# 2AFADC.net
KiCad netlist of a schematic drawn in EAGLE
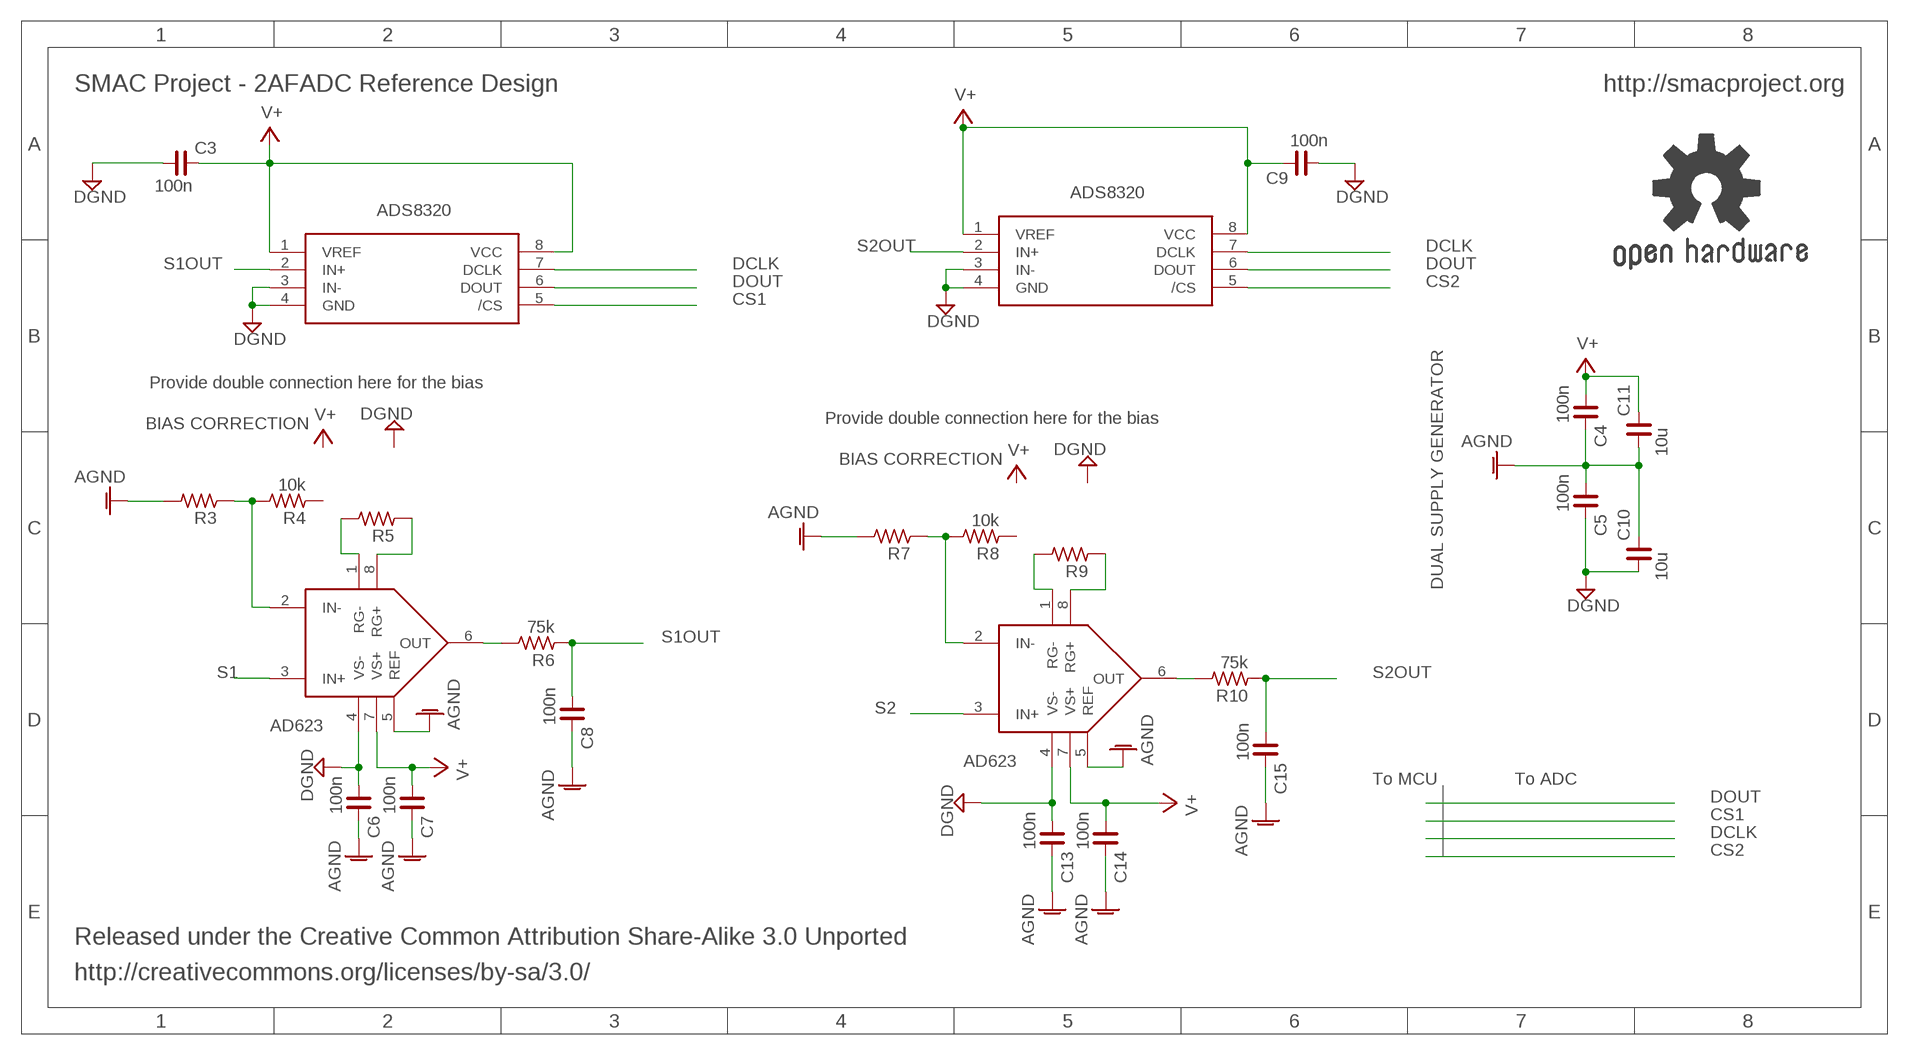
[diagram p0: schematic, sheet 1]

(export (version "E")
  (design (tool "Eeschema 10.0.6"))
  (components
    (comp (ref "C3")
      (value "100n")
      (footprint "eagle-import:C0402")
      (libsource (lib "eagle-import") (part "C_0402"))
    )
    (comp (ref "C4")
      (value "100n")
      (footprint "eagle-import:C0402")
      (libsource (lib "eagle-import") (part "C_0402"))
    )
    (comp (ref "C5")
      (value "100n")
      (footprint "eagle-import:C0402")
      (libsource (lib "eagle-import") (part "C_0402"))
    )
    (comp (ref "C6")
      (value "100n")
      (footprint "eagle-import:C0402")
      (libsource (lib "eagle-import") (part "C_0402"))
    )
    (comp (ref "C7")
      (value "100n")
      (footprint "eagle-import:C0402")
      (libsource (lib "eagle-import") (part "C_0402"))
    )
    (comp (ref "C8")
      (value "100n")
      (footprint "eagle-import:C0402")
      (libsource (lib "eagle-import") (part "C_0402"))
    )
    (comp (ref "C9")
      (value "100n")
      (footprint "eagle-import:C0402")
      (libsource (lib "eagle-import") (part "C_0402"))
    )
    (comp (ref "C10")
      (value "10u")
      (footprint "eagle-import:C0402")
      (libsource (lib "eagle-import") (part "C_0402"))
    )
    (comp (ref "C11")
      (value "10u")
      (footprint "eagle-import:C0402")
      (libsource (lib "eagle-import") (part "C_0402"))
    )
    (comp (ref "C13")
      (value "100n")
      (footprint "eagle-import:C0402")
      (libsource (lib "eagle-import") (part "C_0402"))
    )
    (comp (ref "C14")
      (value "100n")
      (footprint "eagle-import:C0402")
      (libsource (lib "eagle-import") (part "C_0402"))
    )
    (comp (ref "C15")
      (value "100n")
      (footprint "eagle-import:C0402")
      (libsource (lib "eagle-import") (part "C_0402"))
    )
    (comp (ref "GOLD_ORB_SM1")
      (value "OSHWLOGO_REF_SM")
      (footprint "eagle-import:OSHW2REF")
      (libsource (lib "eagle-import") (part "OSHWLOGO_REF_SM"))
    )
    (comp (ref "R3")
      (value "R_0402")
      (footprint "eagle-import:R0402")
      (libsource (lib "eagle-import") (part "R_0402"))
    )
    (comp (ref "R4")
      (value "10k")
      (footprint "eagle-import:R0402")
      (libsource (lib "eagle-import") (part "R_0402"))
    )
    (comp (ref "R5")
      (value "R_0402")
      (footprint "eagle-import:R0402")
      (libsource (lib "eagle-import") (part "R_0402"))
    )
    (comp (ref "R6")
      (value "75k")
      (footprint "eagle-import:R0402")
      (libsource (lib "eagle-import") (part "R_0402"))
    )
    (comp (ref "R7")
      (value "R_0402")
      (footprint "eagle-import:R0402")
      (libsource (lib "eagle-import") (part "R_0402"))
    )
    (comp (ref "R8")
      (value "10k")
      (footprint "eagle-import:R0402")
      (libsource (lib "eagle-import") (part "R_0402"))
    )
    (comp (ref "R9")
      (value "R_0402")
      (footprint "eagle-import:R0402")
      (libsource (lib "eagle-import") (part "R_0402"))
    )
    (comp (ref "R10")
      (value "75k")
      (footprint "eagle-import:R0402")
      (libsource (lib "eagle-import") (part "R_0402"))
    )
    (comp (ref "U$2")
      (value "AD623MSOP8")
      (footprint "eagle-import:MSOP8")
      (libsource (lib "eagle-import") (part "AD623MSOP8"))
    )
    (comp (ref "U$3")
      (value "AD623MSOP8")
      (footprint "eagle-import:MSOP8")
      (libsource (lib "eagle-import") (part "AD623MSOP8"))
    )
    (comp (ref "U$5")
      (value "ADS8320MSOP8")
      (footprint "eagle-import:MSOP8")
      (libsource (lib "eagle-import") (part "ADS8320MSOP8"))
    )
    (comp (ref "U$6")
      (value "ADS8320MSOP8")
      (footprint "eagle-import:MSOP8")
      (libsource (lib "eagle-import") (part "ADS8320MSOP8"))
    )
  )
  (nets
    (net (code "1") (name "/CS1") (class "Default")
      (node (ref "U$5") (pin "5") (pinfunction "/CS_5") (pintype "bidirectional"))
    )
    (net (code "2") (name "/CS2") (class "Default")
      (node (ref "U$6") (pin "5") (pinfunction "/CS_5") (pintype "bidirectional"))
    )
    (net (code "3") (name "/DCLK") (class "Default")
      (node (ref "U$5") (pin "7") (pinfunction "DCLK_7") (pintype "bidirectional"))
      (node (ref "U$6") (pin "7") (pinfunction "DCLK_7") (pintype "bidirectional"))
    )
    (net (code "4") (name "/DOUT") (class "Default")
      (node (ref "U$5") (pin "6") (pinfunction "DOUT_6") (pintype "bidirectional"))
      (node (ref "U$6") (pin "6") (pinfunction "DOUT_6") (pintype "bidirectional"))
    )
    (net (code "5") (name "/S1") (class "Default")
      (node (ref "U$3") (pin "3") (pinfunction "IN+_3") (pintype "bidirectional"))
    )
    (net (code "6") (name "/S1OUT") (class "Default")
      (node (ref "C8") (pin "1") (pinfunction "1_1") (pintype "passive"))
      (node (ref "R6") (pin "1") (pinfunction "1_1") (pintype "passive"))
      (node (ref "U$5") (pin "2") (pinfunction "IN+_2") (pintype "bidirectional"))
    )
    (net (code "7") (name "/S2") (class "Default")
      (node (ref "U$2") (pin "3") (pinfunction "IN+_3") (pintype "bidirectional"))
    )
    (net (code "8") (name "/S2OUT") (class "Default")
      (node (ref "C15") (pin "1") (pinfunction "1_1") (pintype "passive"))
      (node (ref "R10") (pin "1") (pinfunction "1_1") (pintype "passive"))
      (node (ref "U$6") (pin "2") (pinfunction "IN+_2") (pintype "bidirectional"))
    )
    (net (code "9") (name "AGND") (class "Default")
      (node (ref "C10") (pin "2") (pinfunction "2_2") (pintype "passive"))
      (node (ref "C11") (pin "1") (pinfunction "1_1") (pintype "passive"))
      (node (ref "C13") (pin "2") (pinfunction "2_2") (pintype "passive"))
      (node (ref "C14") (pin "2") (pinfunction "2_2") (pintype "passive"))
      (node (ref "C15") (pin "2") (pinfunction "2_2") (pintype "passive"))
      (node (ref "C4") (pin "2") (pinfunction "2_2") (pintype "passive"))
      (node (ref "C5") (pin "1") (pinfunction "1_1") (pintype "passive"))
      (node (ref "C6") (pin "2") (pinfunction "2_2") (pintype "passive"))
      (node (ref "C7") (pin "2") (pinfunction "2_2") (pintype "passive"))
      (node (ref "C8") (pin "2") (pinfunction "2_2") (pintype "passive"))
      (node (ref "R3") (pin "2") (pinfunction "2_2") (pintype "passive"))
      (node (ref "R7") (pin "2") (pinfunction "2_2") (pintype "passive"))
      (node (ref "U$2") (pin "5") (pinfunction "REF_5") (pintype "bidirectional"))
      (node (ref "U$3") (pin "5") (pinfunction "REF_5") (pintype "bidirectional"))
    )
    (net (code "10") (name "DGND") (class "Default")
      (node (ref "C10") (pin "1") (pinfunction "1_1") (pintype "passive"))
      (node (ref "C13") (pin "1") (pinfunction "1_1") (pintype "passive"))
      (node (ref "C3") (pin "1") (pinfunction "1_1") (pintype "passive"))
      (node (ref "C5") (pin "2") (pinfunction "2_2") (pintype "passive"))
      (node (ref "C6") (pin "1") (pinfunction "1_1") (pintype "passive"))
      (node (ref "C9") (pin "1") (pinfunction "1_1") (pintype "passive"))
      (node (ref "U$2") (pin "4") (pinfunction "VS-_4") (pintype "bidirectional"))
      (node (ref "U$3") (pin "4") (pinfunction "VS-_4") (pintype "bidirectional"))
      (node (ref "U$5") (pin "3") (pinfunction "IN-_3") (pintype "bidirectional"))
      (node (ref "U$5") (pin "4") (pinfunction "GND_4") (pintype "bidirectional"))
      (node (ref "U$6") (pin "3") (pinfunction "IN-_3") (pintype "bidirectional"))
      (node (ref "U$6") (pin "4") (pinfunction "GND_4") (pintype "bidirectional"))
    )
    (net (code "11") (name "Net-(U$2-IN-)") (class "Default")
      (node (ref "R7") (pin "1") (pinfunction "1_1") (pintype "passive"))
      (node (ref "R8") (pin "2") (pinfunction "2_2") (pintype "passive"))
      (node (ref "U$2") (pin "2") (pinfunction "IN-_2") (pintype "bidirectional"))
    )
    (net (code "12") (name "Net-(U$2-OUT)") (class "Default")
      (node (ref "R10") (pin "2") (pinfunction "2_2") (pintype "passive"))
      (node (ref "U$2") (pin "6") (pinfunction "OUT_6") (pintype "bidirectional"))
    )
    (net (code "13") (name "Net-(U$2-RG+)") (class "Default")
      (node (ref "R9") (pin "1") (pinfunction "1_1") (pintype "passive"))
      (node (ref "U$2") (pin "8") (pinfunction "RG+_8") (pintype "bidirectional"))
    )
    (net (code "14") (name "Net-(U$2-RG-)") (class "Default")
      (node (ref "R9") (pin "2") (pinfunction "2_2") (pintype "passive"))
      (node (ref "U$2") (pin "1") (pinfunction "RG-_1") (pintype "bidirectional"))
    )
    (net (code "15") (name "Net-(U$3-IN-)") (class "Default")
      (node (ref "R3") (pin "1") (pinfunction "1_1") (pintype "passive"))
      (node (ref "R4") (pin "2") (pinfunction "2_2") (pintype "passive"))
      (node (ref "U$3") (pin "2") (pinfunction "IN-_2") (pintype "bidirectional"))
    )
    (net (code "16") (name "Net-(U$3-OUT)") (class "Default")
      (node (ref "R6") (pin "2") (pinfunction "2_2") (pintype "passive"))
      (node (ref "U$3") (pin "6") (pinfunction "OUT_6") (pintype "bidirectional"))
    )
    (net (code "17") (name "Net-(U$3-RG+)") (class "Default")
      (node (ref "R5") (pin "1") (pinfunction "1_1") (pintype "passive"))
      (node (ref "U$3") (pin "8") (pinfunction "RG+_8") (pintype "bidirectional"))
    )
    (net (code "18") (name "Net-(U$3-RG-)") (class "Default")
      (node (ref "R5") (pin "2") (pinfunction "2_2") (pintype "passive"))
      (node (ref "U$3") (pin "1") (pinfunction "RG-_1") (pintype "bidirectional"))
    )
    (net (code "19") (name "V+") (class "Default")
      (node (ref "C11") (pin "2") (pinfunction "2_2") (pintype "passive"))
      (node (ref "C14") (pin "1") (pinfunction "1_1") (pintype "passive"))
      (node (ref "C3") (pin "2") (pinfunction "2_2") (pintype "passive"))
      (node (ref "C4") (pin "1") (pinfunction "1_1") (pintype "passive"))
      (node (ref "C7") (pin "1") (pinfunction "1_1") (pintype "passive"))
      (node (ref "C9") (pin "2") (pinfunction "2_2") (pintype "passive"))
      (node (ref "U$2") (pin "7") (pinfunction "VS+_7") (pintype "bidirectional"))
      (node (ref "U$3") (pin "7") (pinfunction "VS+_7") (pintype "bidirectional"))
      (node (ref "U$5") (pin "1") (pinfunction "VREF_1") (pintype "bidirectional"))
      (node (ref "U$5") (pin "8") (pinfunction "VCC_8") (pintype "bidirectional"))
      (node (ref "U$6") (pin "1") (pinfunction "VREF_1") (pintype "bidirectional"))
      (node (ref "U$6") (pin "8") (pinfunction "VCC_8") (pintype "bidirectional"))
    )
    (net (code "20") (name "unconnected-(R4-Pad1)") (class "Default")
      (node (ref "R4") (pin "1") (pinfunction "1_1") (pintype "passive"))
    )
    (net (code "21") (name "unconnected-(R8-Pad1)") (class "Default")
      (node (ref "R8") (pin "1") (pinfunction "1_1") (pintype "passive"))
    )
  )
)
